# 04_POWER.net
KiCad netlist of a schematic drawn in Altium Designer
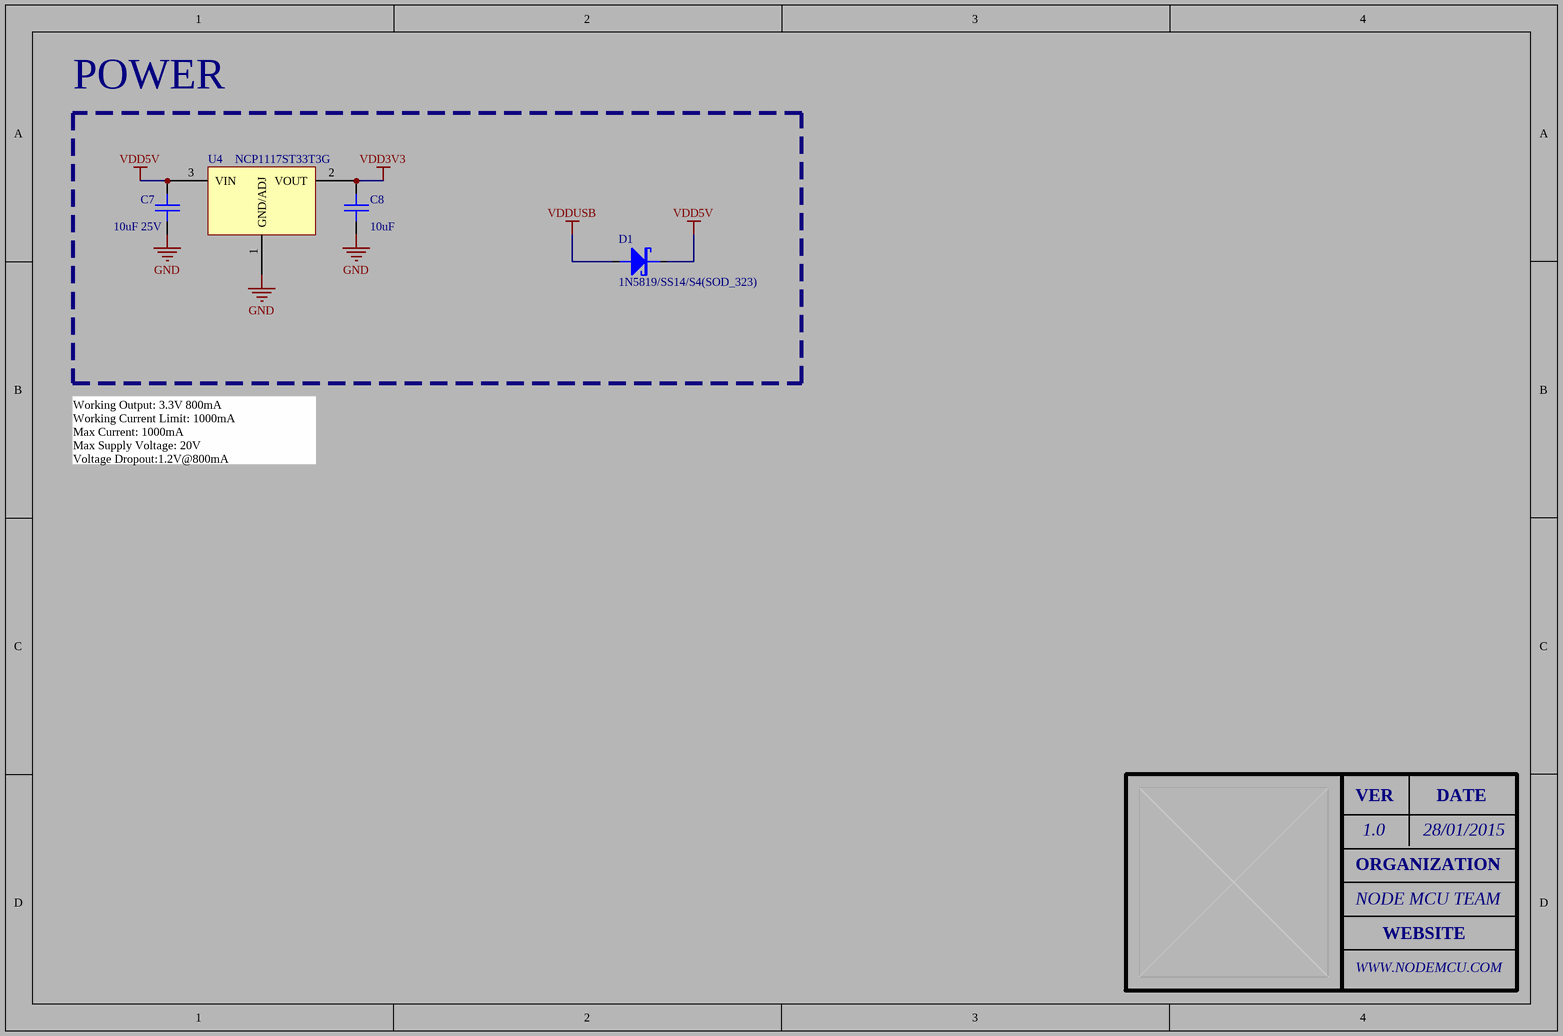
[diagram p0: 04_POWER.SchDoc]

(export (version "E")
  (design (tool "Eeschema 10.0.6"))
  (components
    (comp (ref "C7")
      (value "10uF 25V")
      (footprint "SMT_C_0805")
      (description "Surface mount capacitor 0805")
      (libsource (lib "Vowstar_Basic_Device") (part "SMT_C_0805"))
    )
    (comp (ref "C8")
      (value "10uF")
      (footprint "SMT_C_0402")
      (description "Surface mount capacitor 0402")
      (libsource (lib "Vowstar_Basic_Device") (part "SMT_C_0402"))
    )
    (comp (ref "D1")
      (value "1N5819/SS14/S4(SOD_323)")
      (footprint "SMT_DIODE_SOD_323")
      (description "Surface mount schottky diode SOD-323(0805) Package")
      (libsource (lib "Vowstar_Basic_Device") (part "SMT_DIODE_SCHOTTKY_SOD_323"))
    )
    (comp (ref "U4")
      (value "NCP1117ST33T3G")
      (footprint "SOT-223")
      (description "NCP1117, NCV1117. 1.0 A Low-Dropout Positive  Fixed and Adjustable  Voltage Regulators")
      (libsource (lib "Vowstar_IC_General") (part "NCP1117"))
    )
  )
  (nets
    (net (code "1") (name "GND") (class "Default")
      (node (ref "C7") (pin "2") (pinfunction "2_2") (pintype "passive"))
      (node (ref "C8") (pin "2") (pinfunction "2_2") (pintype "passive"))
      (node (ref "U4") (pin "1") (pinfunction "GND/ADJ_1") (pintype "passive"))
    )
    (net (code "2") (name "VDD3V3") (class "Default")
      (node (ref "C8") (pin "1") (pinfunction "1_1") (pintype "passive"))
      (node (ref "U4") (pin "2") (pinfunction "VOUT_2") (pintype "passive"))
    )
    (net (code "3") (name "VDD5V") (class "Default")
      (node (ref "C7") (pin "1") (pinfunction "1_1") (pintype "passive"))
      (node (ref "D1") (pin "2") (pinfunction "K_2") (pintype "passive"))
      (node (ref "U4") (pin "3") (pinfunction "VIN_3") (pintype "passive"))
    )
    (net (code "4") (name "VDDUSB") (class "Default")
      (node (ref "D1") (pin "1") (pinfunction "A_1") (pintype "passive"))
    )
  )
)
